# Booster.net
KiCad netlist of a schematic drawn in EAGLE
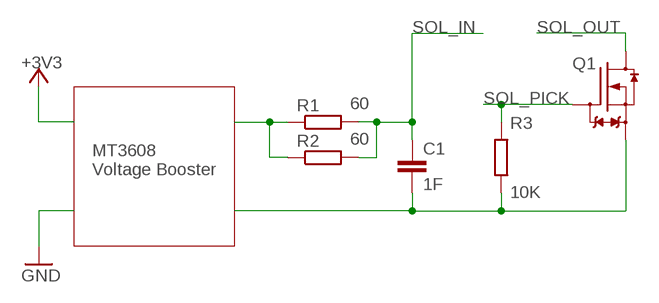
[diagram p0: schematic, sheet 1]

(export (version "E")
  (design (tool "Eeschema 10.0.6"))
  (components
    (comp (ref "C1")
      (value "1F")
      (footprint "eagle-import:0603")
      (libsource (lib "eagle-import") (part "CAP_0603"))
    )
    (comp (ref "Q1")
      (value "SI1308EDL")
      (footprint "eagle-import:SOT-323")
      (libsource (lib "eagle-import") (part "SI1308EDL"))
    )
    (comp (ref "R1")
      (value "60")
      (footprint "eagle-import:0603")
      (libsource (lib "eagle-import") (part "RES_0603"))
    )
    (comp (ref "R2")
      (value "60")
      (footprint "eagle-import:0603")
      (libsource (lib "eagle-import") (part "RES_0603"))
    )
    (comp (ref "R3")
      (value "10K")
      (footprint "eagle-import:0603")
      (libsource (lib "eagle-import") (part "RES_0603"))
    )
  )
  (nets
    (net (code "2") (name "/SOL_IN") (class "Default")
      (node (ref "C1") (pin "1") (pinfunction "1_1") (pintype "passive"))
      (node (ref "R1") (pin "2") (pinfunction "2_2") (pintype "passive"))
      (node (ref "R2") (pin "2") (pinfunction "2_2") (pintype "passive"))
    )
    (net (code "3") (name "/SOL_OUT") (class "Default")
      (node (ref "Q1") (pin "3") (pinfunction "D_3") (pintype "passive"))
    )
    (net (code "4") (name "/SOL_PICK") (class "Default")
      (node (ref "Q1") (pin "1") (pinfunction "G_1") (pintype "passive"))
      (node (ref "R3") (pin "2") (pinfunction "2_2") (pintype "passive"))
    )
    (net (code "6") (name "Net-(Q1-S)") (class "Default")
      (node (ref "C1") (pin "2") (pinfunction "2_2") (pintype "passive"))
      (node (ref "Q1") (pin "2") (pinfunction "S_2") (pintype "passive"))
      (node (ref "R3") (pin "1") (pinfunction "1_1") (pintype "passive"))
    )
    (net (code "7") (name "Net-(R1-Pad1)") (class "Default")
      (node (ref "R1") (pin "1") (pinfunction "1_1") (pintype "passive"))
      (node (ref "R2") (pin "1") (pinfunction "1_1") (pintype "passive"))
    )
  )
)
